# Isolator.net
KiCad netlist of a schematic drawn in Altium Designer
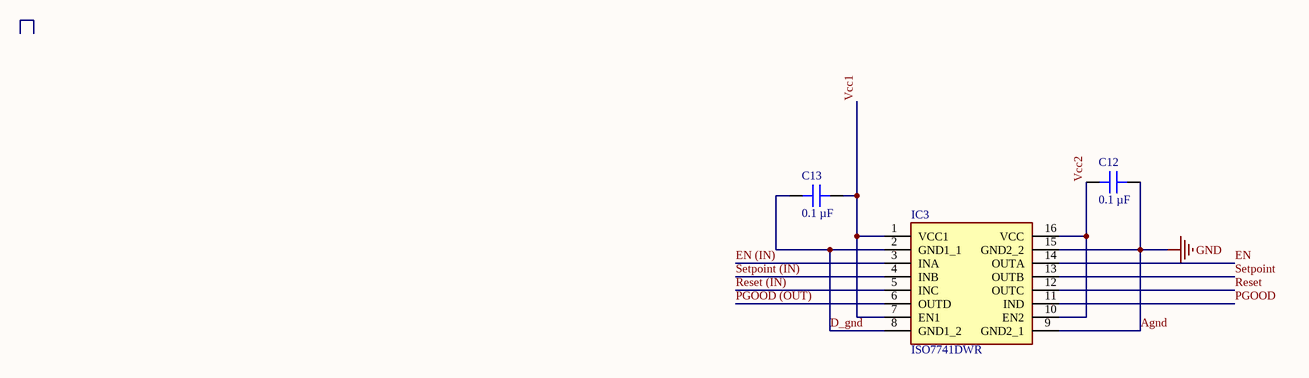
[diagram p0: Isolator.SchDoc]

(export (version "E")
  (design (tool "Eeschema 10.0.6"))
  (components
    (comp (ref "C12")
      (value "0.1 µF")
      (footprint "CAP 0603_1608")
      (description "CAP CER 0.1UF 50V X7R 0603")
      (fields (field (name "PART NUMBER") "C0603C104K5RAC7411") (field (name "MANUFACTURER") "KEMET"))
      (libsource (lib "Celestial Altium Library - altium_library") (part "Capacitor"))
    )
    (comp (ref "C13")
      (value "0.1 µF")
      (footprint "CAP 0603_1608")
      (description "CAP CER 0.1UF 50V X7R 0603")
      (fields (field (name "PART NUMBER") "C0603C104K5RAC7411") (field (name "MANUFACTURER") "KEMET"))
      (libsource (lib "Celestial Altium Library - altium_library") (part "Capacitor"))
    )
    (comp (ref "IC3")
      (value "ISO7741DWR")
      (footprint "SamacSys:SOIC127P1030X265-16N")
      (description "Integrated Circuit")
      (fields (field (name "MOUSER PART NUMBER") "595-ISO7741DWR"))
      (libsource (lib "*") (part "ISO7741DWR"))
    )
  )
  (nets
    (net (code "1") (name "/D_gnd") (class "Default")
      (node (ref "C13") (pin "1") (pinfunction "1_1") (pintype "passive"))
      (node (ref "IC3") (pin "2") (pinfunction "GND1_1_2") (pintype "passive"))
      (node (ref "IC3") (pin "8") (pinfunction "GND1_2_8") (pintype "passive"))
    )
    (net (code "2") (name "/EN") (class "Default")
      (node (ref "IC3") (pin "14") (pinfunction "OUTA_14") (pintype "passive"))
    )
    (net (code "3") (name "/EN (IN)") (class "Default")
      (node (ref "IC3") (pin "3") (pinfunction "INA_3") (pintype "passive"))
    )
    (net (code "4") (name "/PGOOD") (class "Default")
      (node (ref "IC3") (pin "11") (pinfunction "IND_11") (pintype "passive"))
    )
    (net (code "5") (name "/PGOOD (OUT)") (class "Default")
      (node (ref "IC3") (pin "6") (pinfunction "OUTD_6") (pintype "passive"))
    )
    (net (code "6") (name "/Reset") (class "Default")
      (node (ref "IC3") (pin "12") (pinfunction "OUTC_12") (pintype "passive"))
    )
    (net (code "7") (name "/Reset (IN)") (class "Default")
      (node (ref "IC3") (pin "5") (pinfunction "INC_5") (pintype "passive"))
    )
    (net (code "8") (name "/Setpoint") (class "Default")
      (node (ref "IC3") (pin "13") (pinfunction "OUTB_13") (pintype "passive"))
    )
    (net (code "9") (name "/Setpoint (IN)") (class "Default")
      (node (ref "IC3") (pin "4") (pinfunction "INB_4") (pintype "passive"))
    )
    (net (code "10") (name "/Vcc1") (class "Default")
      (node (ref "C13") (pin "2") (pinfunction "2_2") (pintype "passive"))
      (node (ref "IC3") (pin "1") (pinfunction "VCC1_1") (pintype "passive"))
      (node (ref "IC3") (pin "7") (pinfunction "EN1_7") (pintype "passive"))
    )
    (net (code "11") (name "/Vcc2") (class "Default")
      (node (ref "C12") (pin "1") (pinfunction "1_1") (pintype "passive"))
      (node (ref "IC3") (pin "10") (pinfunction "EN2_10") (pintype "passive"))
      (node (ref "IC3") (pin "16") (pinfunction "VCC_16") (pintype "passive"))
    )
    (net (code "12") (name "GND") (class "Default")
      (node (ref "C12") (pin "2") (pinfunction "2_2") (pintype "passive"))
      (node (ref "IC3") (pin "15") (pinfunction "GND2_2_15") (pintype "passive"))
      (node (ref "IC3") (pin "9") (pinfunction "GND2_1_9") (pintype "passive"))
    )
  )
)
